# alarm.net
KiCad netlist of a schematic drawn in Altium Designer
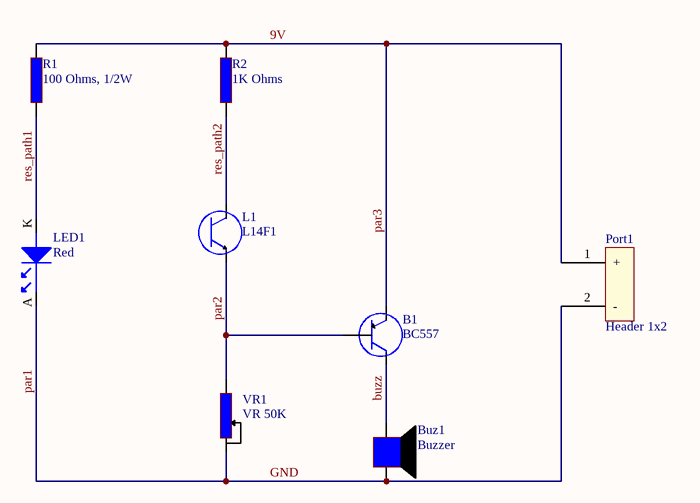
[diagram p0: alarm.SchDoc]

(export (version "E")
  (design (tool "Eeschema 10.0.6"))
  (components
    (comp (ref "B1")
      (value "BC557")
      (footprint "BJT")
      (description "Trans GP BJT PNP 45V 0.1A 3-Pin TO-92 T/R")
      (fields
        (field (name "MANUFACTURER") "ON Semiconductor")
        (field (name "MANUFACTURER PART NUMBER") "BC557BRL1G")
      )
      (libsource (lib "alarm_lib") (part "BC557BRL1G"))
    )
    (comp (ref "Buz1")
      (value "Buzzer")
      (footprint "Buz")
      (description "AUDIO MAGNETIC XDCR 3-7V TH")
      (fields
        (field (name "MANUFACTURER") "Projects Unlimited")
        (field (name "MANUFACTURER PART NUMBER") "AT-1224-TWT-5V-2-R")
      )
      (libsource (lib "alarm_lib") (part "AT-1224-TWT-5V-2-R"))
    )
    (comp (ref "L1")
      (value "L14F1")
      (footprint "phototransistor")
      (description "Photodarlington Chip Silicon 940nm 3-Pin TO-18 Bulk")
      (fields (field (name "MANUFACTURER") "ON Semiconductor / Fairchild"))
      (libsource (lib "alarm_lib") (part "L14F1"))
    )
    (comp (ref "LED1")
      (value "Red")
      (footprint "LED_red")
      (description "On a Reel of 5000, 2.4 V Red LED 1608 (0603) SMD, Lite-On LTST-C191KRKT")
      (fields
        (field (name "MANUFACTURER") "Vishay Lite-On")
        (field (name "MANUFACTURER PART NUMBER") "LTST-C191KRKT")
      )
      (libsource (lib "alarm_lib") (part "LTST-C191KRKT"))
    )
    (comp (ref "Port1")
      (value "Header 1x2")
      (footprint "Port 1x2")
      (description "CONN HEADER VERT 2POS 2.54MM")
      (fields
        (field (name "MANUFACTURER") "TE Connectivity")
        (field (name "MANUFACTURER PART NUMBER") "3-641215-2")
      )
      (libsource (lib "alarm_lib") (part "3-641215-2"))
    )
    (comp (ref "R1")
      (value "100 Ohms, 1/2W")
      (footprint "R100 - duplicate")
      (description "RESISTOR, SURGE, 0805, 1%, 100R")
      (fields
        (field (name "MANUFACTURER") "Panasonic")
        (field (name "MANUFACTURER PART NUMBER") "ERJ-P06F1000V")
      )
      (libsource (lib "alarm_lib") (part "ERJ-P06F1000V"))
    )
    (comp (ref "R2")
      (value "1K Ohms")
      (footprint "R1K")
      (fields
        (field (name "MANUFACTURER") "Panasonic")
        (field (name "MANUFACTURER PART NUMBER") "ERA-2AED102X")
        (field (name "TOLERANCE") "0.5%")
      )
      (libsource (lib "alarm_lib") (part "ERA-2AED102X"))
    )
    (comp (ref "VR1")
      (value "VR 50K")
      (footprint "R1K")
      (description "Slide Potentiometers 50K AUDIO")
      (fields
        (field (name "MANUFACTURER") "Bourns")
        (field (name "MANUFACTURER PART NUMBER") "PTA3043-2010CIA503")
      )
      (libsource (lib "alarm_lib") (part "PTA3043-2010CIA503"))
    )
  )
  (nets
    (net (code "1") (name "/9V") (class "Default")
      (node (ref "B1") (pin "3") (pinfunction "3_3") (pintype "passive"))
      (node (ref "Port1") (pin "1") (pinfunction "+_1") (pintype "passive"))
      (node (ref "R1") (pin "1") (pinfunction "1_1") (pintype "passive"))
      (node (ref "R2") (pin "1") (pinfunction "1_1") (pintype "passive"))
    )
    (net (code "3") (name "/GND") (class "Default")
      (node (ref "Buz1") (pin "2") (pinfunction "2_2") (pintype "passive"))
      (node (ref "LED1") (pin "A") (pinfunction "A_A") (pintype "passive"))
      (node (ref "Port1") (pin "2") (pinfunction "-_2") (pintype "passive"))
      (node (ref "VR1") (pin "2") (pinfunction "2_2") (pintype "passive"))
    )
    (net (code "4") (name "/buzz") (class "Default")
      (node (ref "B1") (pin "5") (pinfunction "5_5") (pintype "passive"))
      (node (ref "Buz1") (pin "1") (pinfunction "1_1") (pintype "passive"))
    )
    (net (code "5") (name "/par2") (class "Default")
      (node (ref "B1") (pin "4") (pinfunction "4_4") (pintype "passive"))
      (node (ref "L1") (pin "2") (pinfunction "2_2") (pintype "passive"))
      (node (ref "VR1") (pin "1") (pinfunction "1_1") (pintype "passive"))
    )
    (net (code "6") (name "/res_path1") (class "Default")
      (node (ref "LED1") (pin "K") (pinfunction "K_K") (pintype "passive"))
      (node (ref "R1") (pin "2") (pinfunction "2_2") (pintype "passive"))
    )
    (net (code "7") (name "/res_path2") (class "Default")
      (node (ref "L1") (pin "1") (pinfunction "1_1") (pintype "passive"))
      (node (ref "R2") (pin "2") (pinfunction "2_2") (pintype "passive"))
    )
  )
)
